# io.net
KiCad netlist of a schematic drawn in Altium Designer
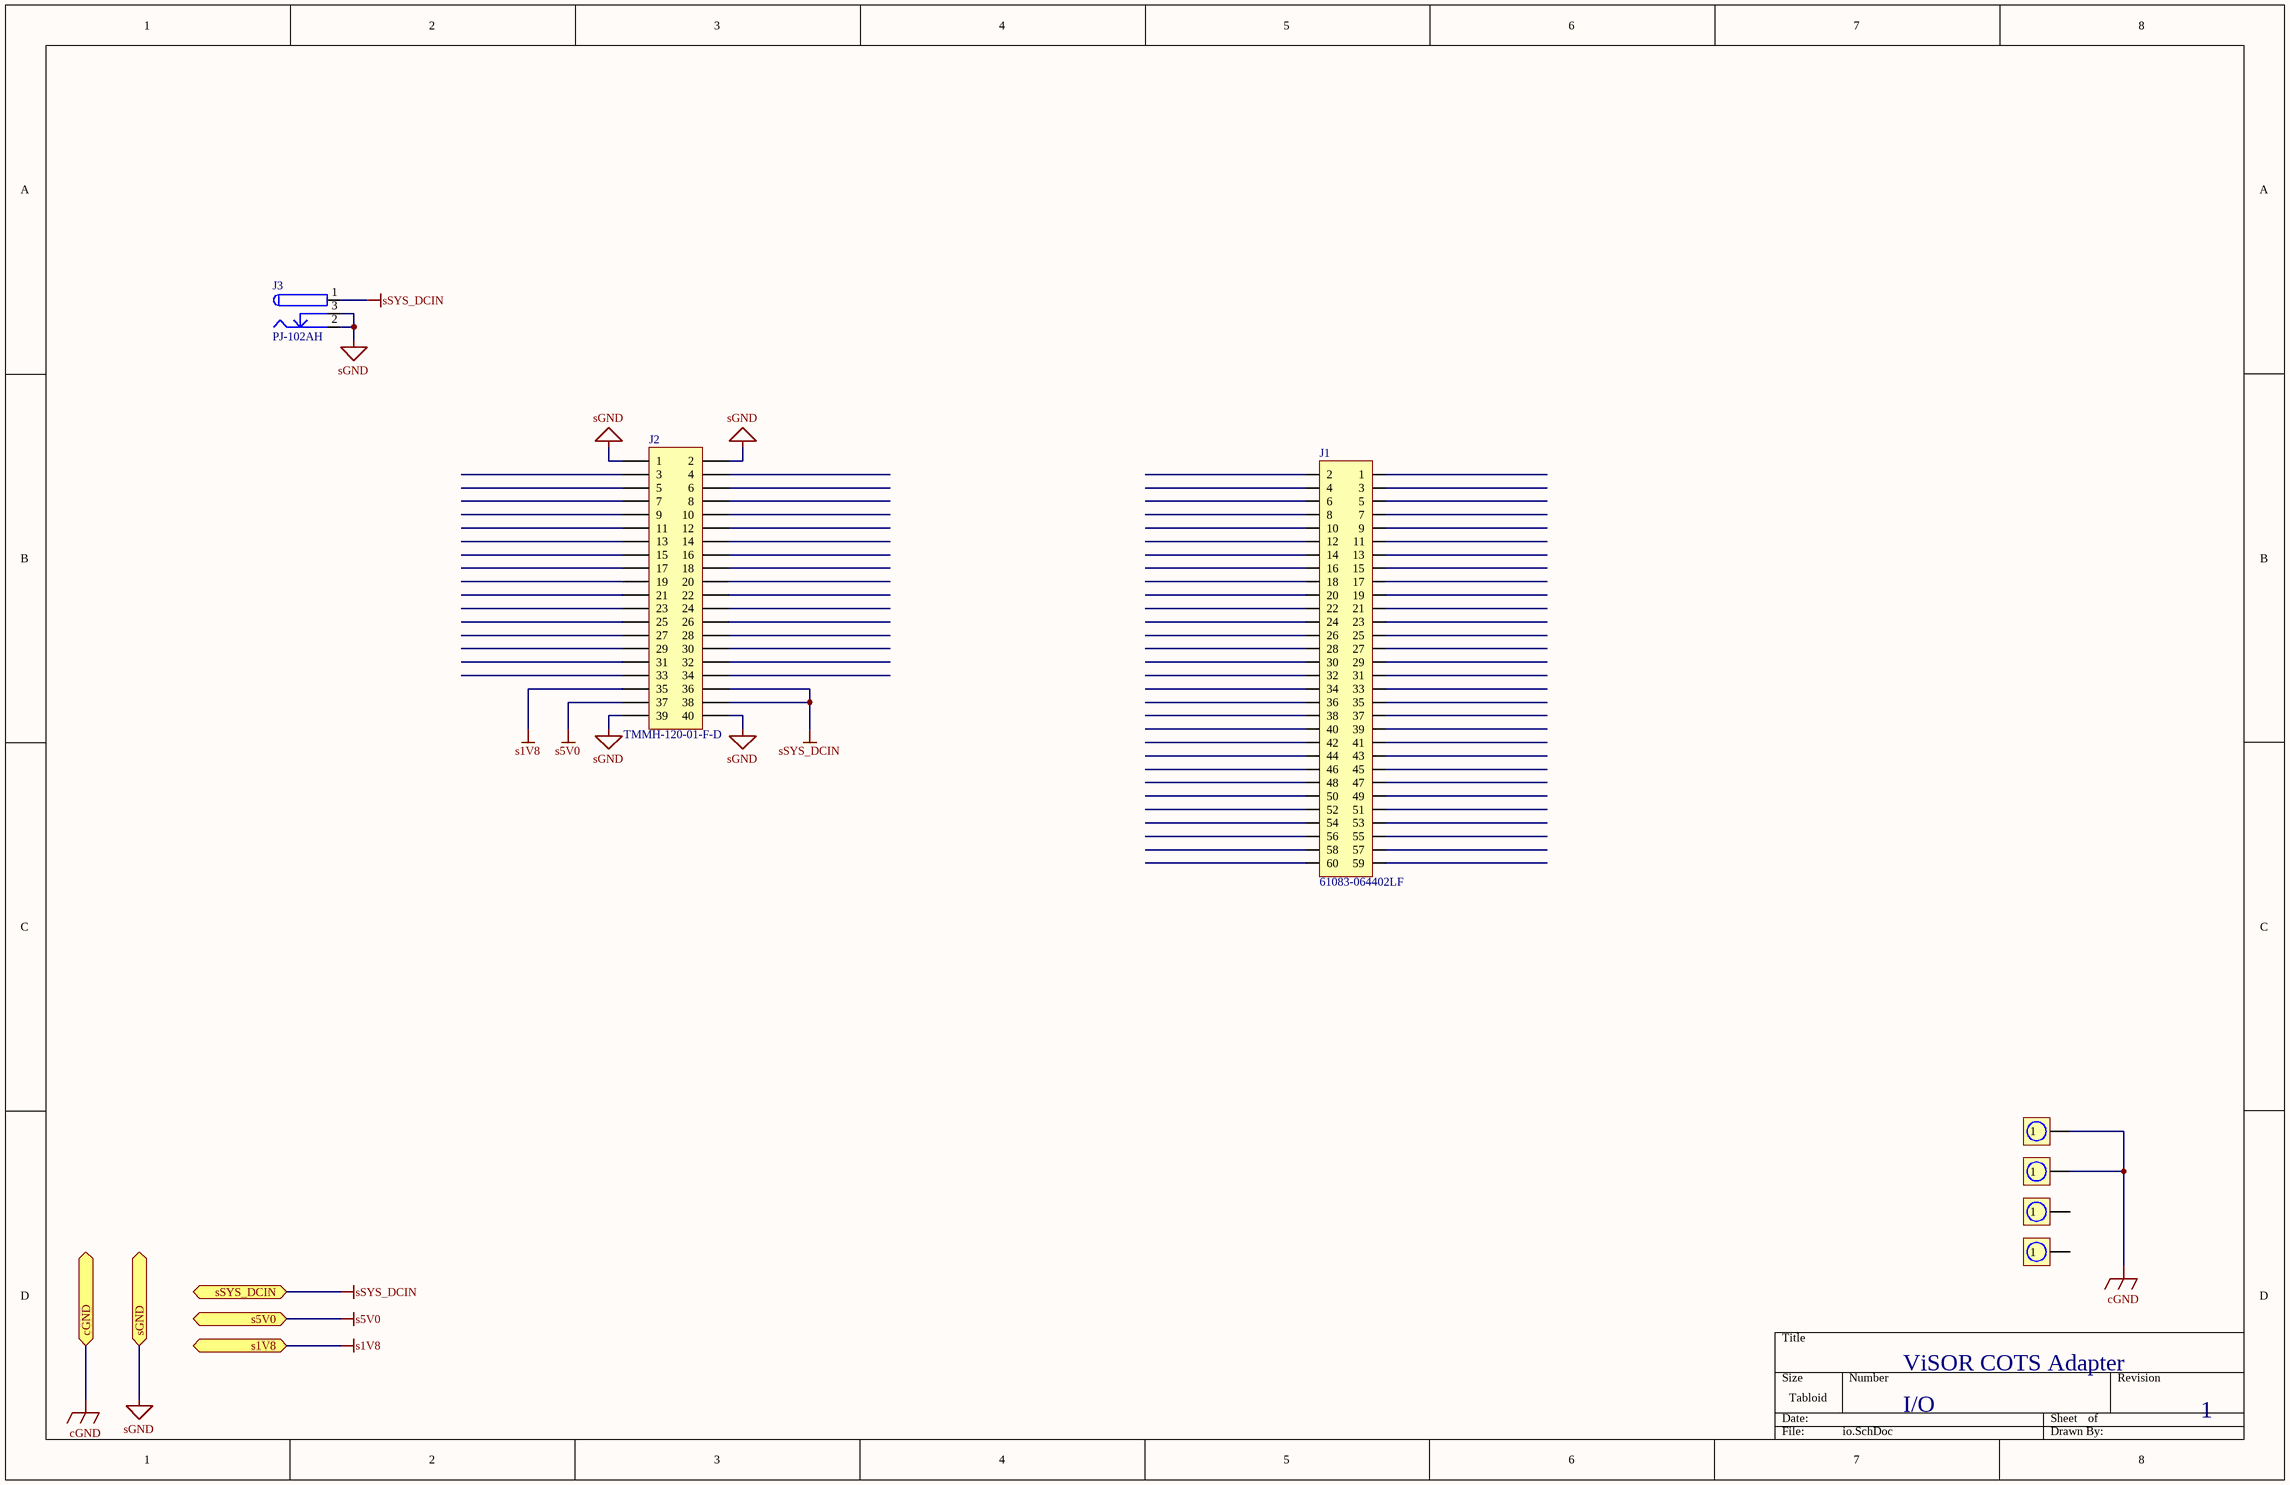
[diagram p0: io.SchDoc]

(export (version "E")
  (design (tool "Eeschema 10.0.6"))
  (components
    (comp (ref "J1")
      (value "61083-064402LF")
      (footprint "61083-064402LF")
      (libsource (lib "fci") (part "61083-064402LF"))
    )
    (comp (ref "J2")
      (value "TMMH-120-01-F-D")
      (footprint "HDR2X20.Metric")
      (description "Header, 2x20-Pin, Dual row, Metric")
      (libsource (lib "samtec") (part "TMMH-120-01-F-D"))
    )
    (comp (ref "J3")
      (value "PJ-102AH")
      (footprint "PJ-102AH")
      (description "Low Voltage Power Supply Connector, 2.1 mm")
      (libsource (lib "cui") (part "PJ-102AH"))
    )
    (comp (ref "M1")
      (value "Mount")
      (footprint "MOUNT_PLATED-M2.5")
      (description "Mounting Point for M2.5 Screw")
      (libsource (lib "common") (part "Mount-M2.5"))
    )
    (comp (ref "M2")
      (value "Mount")
      (footprint "MOUNT_PLATED-M2.5")
      (description "Mounting Point for M2.5 Screw")
      (libsource (lib "common") (part "Mount-M2.5"))
    )
    (comp (ref "M3")
      (value "Mount")
      (footprint "MOUNT_UNPLATED-M2.5")
      (description "Mounting Point for M2.5 Screw")
      (libsource (lib "common") (part "Mount-M2.5"))
    )
    (comp (ref "M4")
      (value "Mount")
      (footprint "MOUNT_UNPLATED-M2.5")
      (description "Mounting Point for M2.5 Screw")
      (libsource (lib "common") (part "Mount-M2.5"))
    )
  )
  (nets
    (net (code "1") (name "cGND") (class "Default")
      (node (ref "M1") (pin "1") (pinfunction "1_1") (pintype "passive"))
      (node (ref "M2") (pin "1") (pinfunction "1_1") (pintype "passive"))
    )
    (net (code "2") (name "s1V8") (class "Default")
      (node (ref "J2") (pin "35") (pinfunction "35_35") (pintype "passive"))
    )
    (net (code "3") (name "s5V0") (class "Default")
      (node (ref "J2") (pin "37") (pinfunction "37_37") (pintype "passive"))
    )
    (net (code "4") (name "sGND") (class "Default")
      (node (ref "J2") (pin "1") (pinfunction "1_1") (pintype "passive"))
      (node (ref "J2") (pin "2") (pinfunction "2_2") (pintype "passive"))
      (node (ref "J2") (pin "39") (pinfunction "39_39") (pintype "passive"))
      (node (ref "J2") (pin "40") (pinfunction "40_40") (pintype "passive"))
      (node (ref "J3") (pin "2") (pinfunction "2_2") (pintype "power_in"))
      (node (ref "J3") (pin "3") (pinfunction "3_3") (pintype "power_in"))
    )
    (net (code "5") (name "sSYS_DCIN") (class "Default")
      (node (ref "J2") (pin "36") (pinfunction "36_36") (pintype "passive"))
      (node (ref "J2") (pin "38") (pinfunction "38_38") (pintype "passive"))
      (node (ref "J3") (pin "1") (pinfunction "1_1") (pintype "power_in"))
    )
    (net (code "6") (name "unconnected-(J1-Pad1)") (class "Default")
      (node (ref "J1") (pin "1") (pinfunction "1_1") (pintype "passive"))
    )
    (net (code "7") (name "unconnected-(J1-Pad2)") (class "Default")
      (node (ref "J1") (pin "2") (pinfunction "2_2") (pintype "passive"))
    )
    (net (code "8") (name "unconnected-(J1-Pad3)") (class "Default")
      (node (ref "J1") (pin "3") (pinfunction "3_3") (pintype "passive"))
    )
    (net (code "9") (name "unconnected-(J1-Pad4)") (class "Default")
      (node (ref "J1") (pin "4") (pinfunction "4_4") (pintype "passive"))
    )
    (net (code "10") (name "unconnected-(J1-Pad5)") (class "Default")
      (node (ref "J1") (pin "5") (pinfunction "5_5") (pintype "passive"))
    )
    (net (code "11") (name "unconnected-(J1-Pad6)") (class "Default")
      (node (ref "J1") (pin "6") (pinfunction "6_6") (pintype "passive"))
    )
    (net (code "12") (name "unconnected-(J1-Pad7)") (class "Default")
      (node (ref "J1") (pin "7") (pinfunction "7_7") (pintype "passive"))
    )
    (net (code "13") (name "unconnected-(J1-Pad8)") (class "Default")
      (node (ref "J1") (pin "8") (pinfunction "8_8") (pintype "passive"))
    )
    (net (code "14") (name "unconnected-(J1-Pad9)") (class "Default")
      (node (ref "J1") (pin "9") (pinfunction "9_9") (pintype "passive"))
    )
    (net (code "15") (name "unconnected-(J1-Pad10)") (class "Default")
      (node (ref "J1") (pin "10") (pinfunction "10_10") (pintype "passive"))
    )
    (net (code "16") (name "unconnected-(J1-Pad11)") (class "Default")
      (node (ref "J1") (pin "11") (pinfunction "11_11") (pintype "passive"))
    )
    (net (code "17") (name "unconnected-(J1-Pad12)") (class "Default")
      (node (ref "J1") (pin "12") (pinfunction "12_12") (pintype "passive"))
    )
    (net (code "18") (name "unconnected-(J1-Pad13)") (class "Default")
      (node (ref "J1") (pin "13") (pinfunction "13_13") (pintype "passive"))
    )
    (net (code "19") (name "unconnected-(J1-Pad14)") (class "Default")
      (node (ref "J1") (pin "14") (pinfunction "14_14") (pintype "passive"))
    )
    (net (code "20") (name "unconnected-(J1-Pad15)") (class "Default")
      (node (ref "J1") (pin "15") (pinfunction "15_15") (pintype "passive"))
    )
    (net (code "21") (name "unconnected-(J1-Pad16)") (class "Default")
      (node (ref "J1") (pin "16") (pinfunction "16_16") (pintype "passive"))
    )
    (net (code "22") (name "unconnected-(J1-Pad17)") (class "Default")
      (node (ref "J1") (pin "17") (pinfunction "17_17") (pintype "passive"))
    )
    (net (code "23") (name "unconnected-(J1-Pad18)") (class "Default")
      (node (ref "J1") (pin "18") (pinfunction "18_18") (pintype "passive"))
    )
    (net (code "24") (name "unconnected-(J1-Pad19)") (class "Default")
      (node (ref "J1") (pin "19") (pinfunction "19_19") (pintype "passive"))
    )
    (net (code "25") (name "unconnected-(J1-Pad20)") (class "Default")
      (node (ref "J1") (pin "20") (pinfunction "20_20") (pintype "passive"))
    )
    (net (code "26") (name "unconnected-(J1-Pad21)") (class "Default")
      (node (ref "J1") (pin "21") (pinfunction "21_21") (pintype "passive"))
    )
    (net (code "27") (name "unconnected-(J1-Pad22)") (class "Default")
      (node (ref "J1") (pin "22") (pinfunction "22_22") (pintype "passive"))
    )
    (net (code "28") (name "unconnected-(J1-Pad23)") (class "Default")
      (node (ref "J1") (pin "23") (pinfunction "23_23") (pintype "passive"))
    )
    (net (code "29") (name "unconnected-(J1-Pad24)") (class "Default")
      (node (ref "J1") (pin "24") (pinfunction "24_24") (pintype "passive"))
    )
    (net (code "30") (name "unconnected-(J1-Pad25)") (class "Default")
      (node (ref "J1") (pin "25") (pinfunction "25_25") (pintype "passive"))
    )
    (net (code "31") (name "unconnected-(J1-Pad26)") (class "Default")
      (node (ref "J1") (pin "26") (pinfunction "26_26") (pintype "passive"))
    )
    (net (code "32") (name "unconnected-(J1-Pad27)") (class "Default")
      (node (ref "J1") (pin "27") (pinfunction "27_27") (pintype "passive"))
    )
    (net (code "33") (name "unconnected-(J1-Pad28)") (class "Default")
      (node (ref "J1") (pin "28") (pinfunction "28_28") (pintype "passive"))
    )
    (net (code "34") (name "unconnected-(J1-Pad29)") (class "Default")
      (node (ref "J1") (pin "29") (pinfunction "29_29") (pintype "passive"))
    )
    (net (code "35") (name "unconnected-(J1-Pad30)") (class "Default")
      (node (ref "J1") (pin "30") (pinfunction "30_30") (pintype "passive"))
    )
    (net (code "36") (name "unconnected-(J1-Pad31)") (class "Default")
      (node (ref "J1") (pin "31") (pinfunction "31_31") (pintype "passive"))
    )
    (net (code "37") (name "unconnected-(J1-Pad32)") (class "Default")
      (node (ref "J1") (pin "32") (pinfunction "32_32") (pintype "passive"))
    )
    (net (code "38") (name "unconnected-(J1-Pad33)") (class "Default")
      (node (ref "J1") (pin "33") (pinfunction "33_33") (pintype "passive"))
    )
    (net (code "39") (name "unconnected-(J1-Pad34)") (class "Default")
      (node (ref "J1") (pin "34") (pinfunction "34_34") (pintype "passive"))
    )
    (net (code "40") (name "unconnected-(J1-Pad35)") (class "Default")
      (node (ref "J1") (pin "35") (pinfunction "35_35") (pintype "passive"))
    )
    (net (code "41") (name "unconnected-(J1-Pad36)") (class "Default")
      (node (ref "J1") (pin "36") (pinfunction "36_36") (pintype "passive"))
    )
    (net (code "42") (name "unconnected-(J1-Pad37)") (class "Default")
      (node (ref "J1") (pin "37") (pinfunction "37_37") (pintype "passive"))
    )
    (net (code "43") (name "unconnected-(J1-Pad38)") (class "Default")
      (node (ref "J1") (pin "38") (pinfunction "38_38") (pintype "passive"))
    )
    (net (code "44") (name "unconnected-(J1-Pad39)") (class "Default")
      (node (ref "J1") (pin "39") (pinfunction "39_39") (pintype "passive"))
    )
    (net (code "45") (name "unconnected-(J1-Pad40)") (class "Default")
      (node (ref "J1") (pin "40") (pinfunction "40_40") (pintype "passive"))
    )
    (net (code "46") (name "unconnected-(J1-Pad41)") (class "Default")
      (node (ref "J1") (pin "41") (pinfunction "41_41") (pintype "passive"))
    )
    (net (code "47") (name "unconnected-(J1-Pad42)") (class "Default")
      (node (ref "J1") (pin "42") (pinfunction "42_42") (pintype "passive"))
    )
    (net (code "48") (name "unconnected-(J1-Pad43)") (class "Default")
      (node (ref "J1") (pin "43") (pinfunction "43_43") (pintype "passive"))
    )
    (net (code "49") (name "unconnected-(J1-Pad44)") (class "Default")
      (node (ref "J1") (pin "44") (pinfunction "44_44") (pintype "passive"))
    )
    (net (code "50") (name "unconnected-(J1-Pad45)") (class "Default")
      (node (ref "J1") (pin "45") (pinfunction "45_45") (pintype "passive"))
    )
    (net (code "51") (name "unconnected-(J1-Pad46)") (class "Default")
      (node (ref "J1") (pin "46") (pinfunction "46_46") (pintype "passive"))
    )
    (net (code "52") (name "unconnected-(J1-Pad47)") (class "Default")
      (node (ref "J1") (pin "47") (pinfunction "47_47") (pintype "passive"))
    )
    (net (code "53") (name "unconnected-(J1-Pad48)") (class "Default")
      (node (ref "J1") (pin "48") (pinfunction "48_48") (pintype "passive"))
    )
    (net (code "54") (name "unconnected-(J1-Pad49)") (class "Default")
      (node (ref "J1") (pin "49") (pinfunction "49_49") (pintype "passive"))
    )
    (net (code "55") (name "unconnected-(J1-Pad50)") (class "Default")
      (node (ref "J1") (pin "50") (pinfunction "50_50") (pintype "passive"))
    )
    (net (code "56") (name "unconnected-(J1-Pad51)") (class "Default")
      (node (ref "J1") (pin "51") (pinfunction "51_51") (pintype "passive"))
    )
    (net (code "57") (name "unconnected-(J1-Pad52)") (class "Default")
      (node (ref "J1") (pin "52") (pinfunction "52_52") (pintype "passive"))
    )
    (net (code "58") (name "unconnected-(J1-Pad53)") (class "Default")
      (node (ref "J1") (pin "53") (pinfunction "53_53") (pintype "passive"))
    )
    (net (code "59") (name "unconnected-(J1-Pad54)") (class "Default")
      (node (ref "J1") (pin "54") (pinfunction "54_54") (pintype "passive"))
    )
    (net (code "60") (name "unconnected-(J1-Pad55)") (class "Default")
      (node (ref "J1") (pin "55") (pinfunction "55_55") (pintype "passive"))
    )
    (net (code "61") (name "unconnected-(J1-Pad56)") (class "Default")
      (node (ref "J1") (pin "56") (pinfunction "56_56") (pintype "passive"))
    )
    (net (code "62") (name "unconnected-(J1-Pad57)") (class "Default")
      (node (ref "J1") (pin "57") (pinfunction "57_57") (pintype "passive"))
    )
    (net (code "63") (name "unconnected-(J1-Pad58)") (class "Default")
      (node (ref "J1") (pin "58") (pinfunction "58_58") (pintype "passive"))
    )
    (net (code "64") (name "unconnected-(J1-Pad59)") (class "Default")
      (node (ref "J1") (pin "59") (pinfunction "59_59") (pintype "passive"))
    )
    (net (code "65") (name "unconnected-(J1-Pad60)") (class "Default")
      (node (ref "J1") (pin "60") (pinfunction "60_60") (pintype "passive"))
    )
    (net (code "66") (name "unconnected-(J2-Pad3)") (class "Default")
      (node (ref "J2") (pin "3") (pinfunction "3_3") (pintype "passive"))
    )
    (net (code "67") (name "unconnected-(J2-Pad4)") (class "Default")
      (node (ref "J2") (pin "4") (pinfunction "4_4") (pintype "passive"))
    )
    (net (code "68") (name "unconnected-(J2-Pad5)") (class "Default")
      (node (ref "J2") (pin "5") (pinfunction "5_5") (pintype "passive"))
    )
    (net (code "69") (name "unconnected-(J2-Pad6)") (class "Default")
      (node (ref "J2") (pin "6") (pinfunction "6_6") (pintype "passive"))
    )
    (net (code "70") (name "unconnected-(J2-Pad7)") (class "Default")
      (node (ref "J2") (pin "7") (pinfunction "7_7") (pintype "passive"))
    )
    (net (code "71") (name "unconnected-(J2-Pad8)") (class "Default")
      (node (ref "J2") (pin "8") (pinfunction "8_8") (pintype "passive"))
    )
    (net (code "72") (name "unconnected-(J2-Pad9)") (class "Default")
      (node (ref "J2") (pin "9") (pinfunction "9_9") (pintype "passive"))
    )
    (net (code "73") (name "unconnected-(J2-Pad10)") (class "Default")
      (node (ref "J2") (pin "10") (pinfunction "10_10") (pintype "passive"))
    )
    (net (code "74") (name "unconnected-(J2-Pad11)") (class "Default")
      (node (ref "J2") (pin "11") (pinfunction "11_11") (pintype "passive"))
    )
    (net (code "75") (name "unconnected-(J2-Pad12)") (class "Default")
      (node (ref "J2") (pin "12") (pinfunction "12_12") (pintype "passive"))
    )
    (net (code "76") (name "unconnected-(J2-Pad13)") (class "Default")
      (node (ref "J2") (pin "13") (pinfunction "13_13") (pintype "passive"))
    )
    (net (code "77") (name "unconnected-(J2-Pad14)") (class "Default")
      (node (ref "J2") (pin "14") (pinfunction "14_14") (pintype "passive"))
    )
    (net (code "78") (name "unconnected-(J2-Pad15)") (class "Default")
      (node (ref "J2") (pin "15") (pinfunction "15_15") (pintype "passive"))
    )
    (net (code "79") (name "unconnected-(J2-Pad16)") (class "Default")
      (node (ref "J2") (pin "16") (pinfunction "16_16") (pintype "passive"))
    )
    (net (code "80") (name "unconnected-(J2-Pad17)") (class "Default")
      (node (ref "J2") (pin "17") (pinfunction "17_17") (pintype "passive"))
    )
    (net (code "81") (name "unconnected-(J2-Pad18)") (class "Default")
      (node (ref "J2") (pin "18") (pinfunction "18_18") (pintype "passive"))
    )
    (net (code "82") (name "unconnected-(J2-Pad19)") (class "Default")
      (node (ref "J2") (pin "19") (pinfunction "19_19") (pintype "passive"))
    )
    (net (code "83") (name "unconnected-(J2-Pad20)") (class "Default")
      (node (ref "J2") (pin "20") (pinfunction "20_20") (pintype "passive"))
    )
    (net (code "84") (name "unconnected-(J2-Pad21)") (class "Default")
      (node (ref "J2") (pin "21") (pinfunction "21_21") (pintype "passive"))
    )
    (net (code "85") (name "unconnected-(J2-Pad22)") (class "Default")
      (node (ref "J2") (pin "22") (pinfunction "22_22") (pintype "passive"))
    )
    (net (code "86") (name "unconnected-(J2-Pad23)") (class "Default")
      (node (ref "J2") (pin "23") (pinfunction "23_23") (pintype "passive"))
    )
    (net (code "87") (name "unconnected-(J2-Pad24)") (class "Default")
      (node (ref "J2") (pin "24") (pinfunction "24_24") (pintype "passive"))
    )
    (net (code "88") (name "unconnected-(J2-Pad25)") (class "Default")
      (node (ref "J2") (pin "25") (pinfunction "25_25") (pintype "passive"))
    )
    (net (code "89") (name "unconnected-(J2-Pad26)") (class "Default")
      (node (ref "J2") (pin "26") (pinfunction "26_26") (pintype "passive"))
    )
    (net (code "90") (name "unconnected-(J2-Pad27)") (class "Default")
      (node (ref "J2") (pin "27") (pinfunction "27_27") (pintype "passive"))
    )
    (net (code "91") (name "unconnected-(J2-Pad28)") (class "Default")
      (node (ref "J2") (pin "28") (pinfunction "28_28") (pintype "passive"))
    )
    (net (code "92") (name "unconnected-(J2-Pad29)") (class "Default")
      (node (ref "J2") (pin "29") (pinfunction "29_29") (pintype "passive"))
    )
    (net (code "93") (name "unconnected-(J2-Pad30)") (class "Default")
      (node (ref "J2") (pin "30") (pinfunction "30_30") (pintype "passive"))
    )
    (net (code "94") (name "unconnected-(J2-Pad31)") (class "Default")
      (node (ref "J2") (pin "31") (pinfunction "31_31") (pintype "passive"))
    )
    (net (code "95") (name "unconnected-(J2-Pad32)") (class "Default")
      (node (ref "J2") (pin "32") (pinfunction "32_32") (pintype "passive"))
    )
    (net (code "96") (name "unconnected-(J2-Pad33)") (class "Default")
      (node (ref "J2") (pin "33") (pinfunction "33_33") (pintype "passive"))
    )
    (net (code "97") (name "unconnected-(J2-Pad34)") (class "Default")
      (node (ref "J2") (pin "34") (pinfunction "34_34") (pintype "passive"))
    )
    (net (code "98") (name "unconnected-(M3-Pad1)") (class "Default")
      (node (ref "M3") (pin "1") (pinfunction "1_1") (pintype "passive"))
    )
    (net (code "99") (name "unconnected-(M4-Pad1)") (class "Default")
      (node (ref "M4") (pin "1") (pinfunction "1_1") (pintype "passive"))
    )
  )
)
